# ButtonBreakout.net
KiCad netlist of a schematic drawn in EAGLE
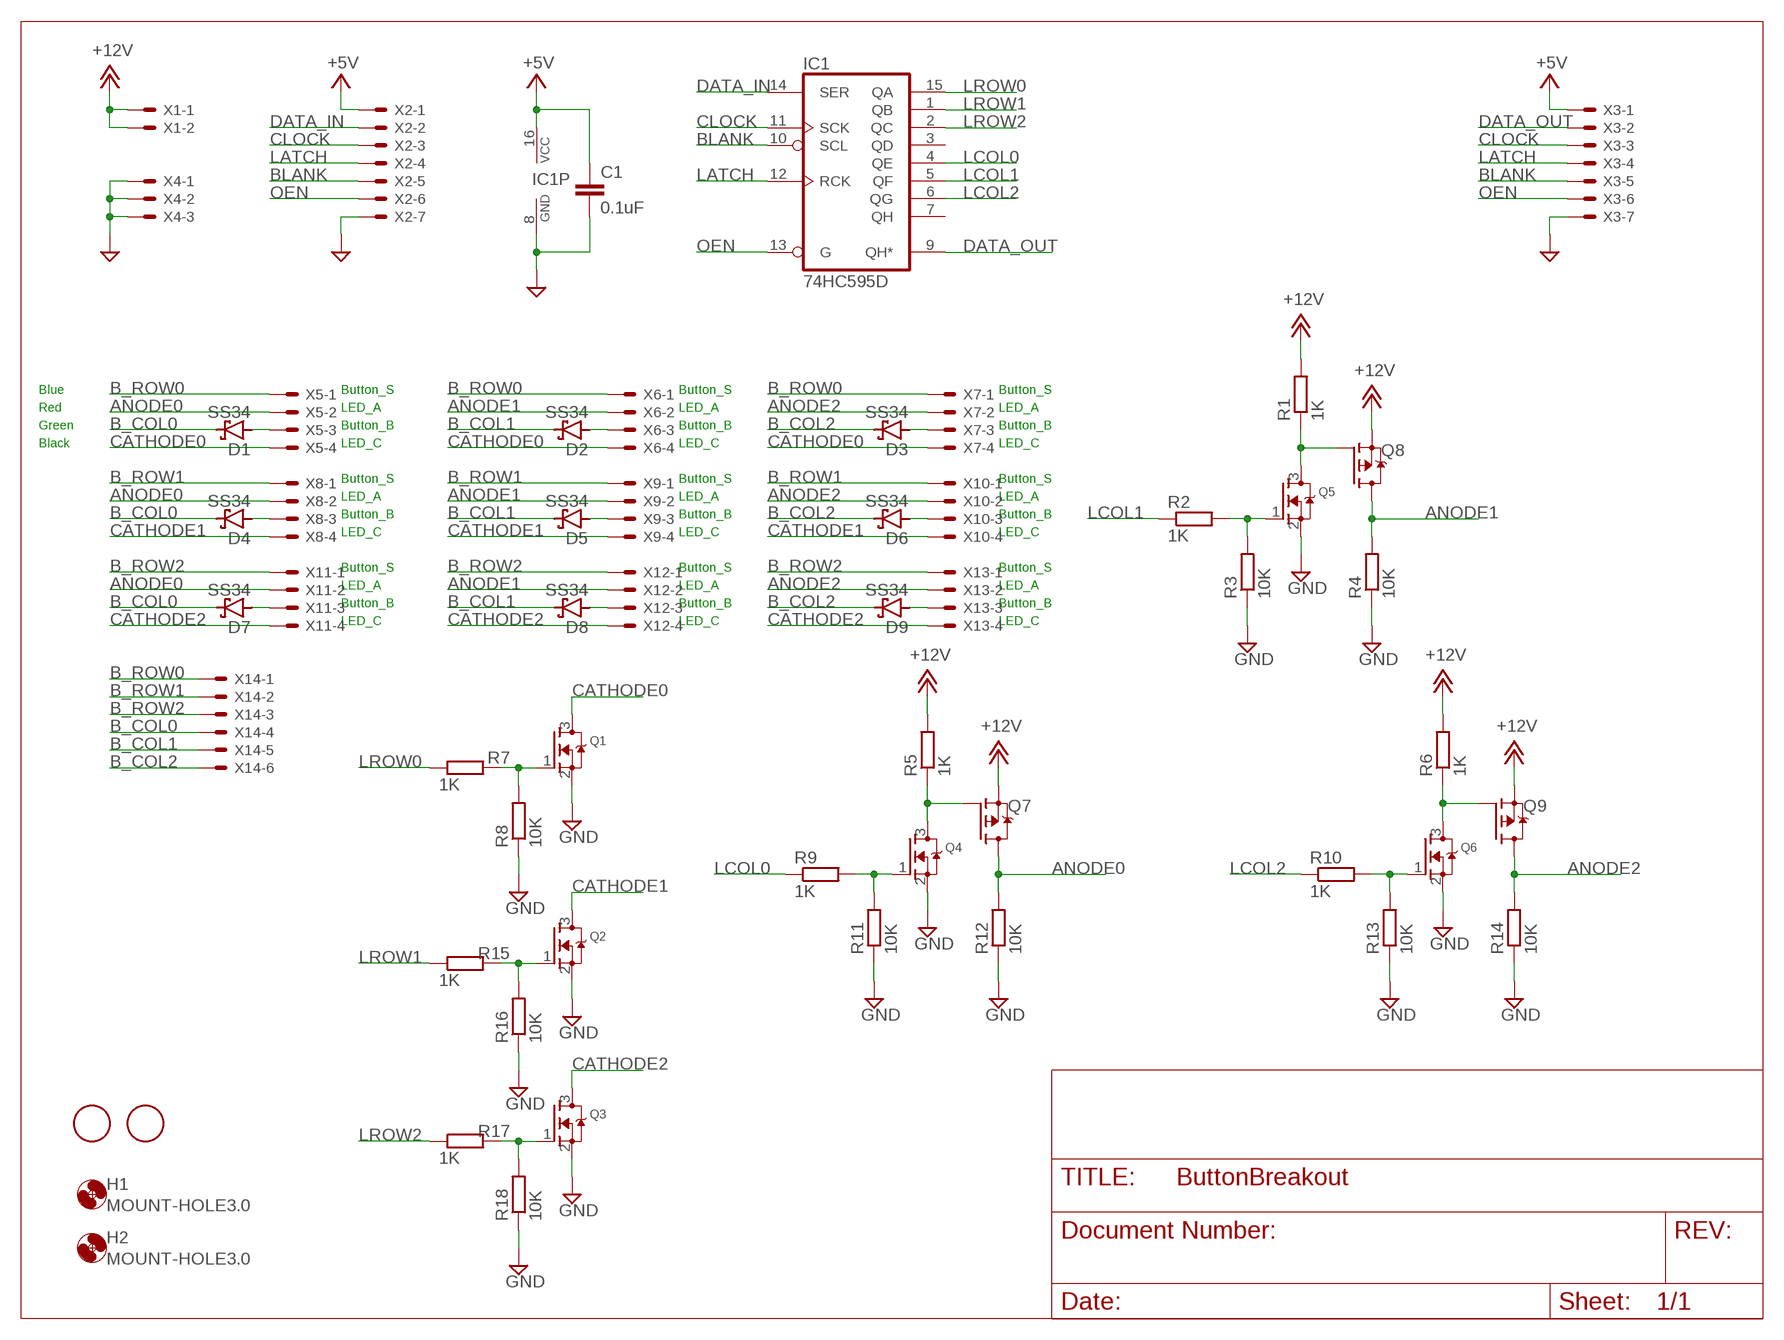
[diagram p0: schematic, sheet 1]

(export (version "E")
  (design (tool "Eeschema 10.0.6"))
  (components
    (comp (ref "C1")
      (value "0.1uF")
      (footprint "eagle-import:C0805")
      (libsource (lib "eagle-import") (part "C-EUC0805"))
    )
    (comp (ref "D1")
      (value "SS34")
      (footprint "eagle-import:SMA")
      (libsource (lib "eagle-import") (part "SS34"))
    )
    (comp (ref "D2")
      (value "SS34")
      (footprint "eagle-import:SMA")
      (libsource (lib "eagle-import") (part "SS34"))
    )
    (comp (ref "D3")
      (value "SS34")
      (footprint "eagle-import:SMA")
      (libsource (lib "eagle-import") (part "SS34"))
    )
    (comp (ref "D4")
      (value "SS34")
      (footprint "eagle-import:SMA")
      (libsource (lib "eagle-import") (part "SS34"))
    )
    (comp (ref "D5")
      (value "SS34")
      (footprint "eagle-import:SMA")
      (libsource (lib "eagle-import") (part "SS34"))
    )
    (comp (ref "D6")
      (value "SS34")
      (footprint "eagle-import:SMA")
      (libsource (lib "eagle-import") (part "SS34"))
    )
    (comp (ref "D7")
      (value "SS34")
      (footprint "eagle-import:SMA")
      (libsource (lib "eagle-import") (part "SS34"))
    )
    (comp (ref "D8")
      (value "SS34")
      (footprint "eagle-import:SMA")
      (libsource (lib "eagle-import") (part "SS34"))
    )
    (comp (ref "D9")
      (value "SS34")
      (footprint "eagle-import:SMA")
      (libsource (lib "eagle-import") (part "SS34"))
    )
    (comp (ref "F1")
      (value "FIDUCIAL")
      (footprint "eagle-import:FIDUCIAL_1MM")
      (libsource (lib "eagle-import") (part "FIDUCIAL"))
    )
    (comp (ref "F2")
      (value "FIDUCIAL")
      (footprint "eagle-import:FIDUCIAL_1MM")
      (libsource (lib "eagle-import") (part "FIDUCIAL"))
    )
    (comp (ref "H1")
      (value "MOUNT-HOLE3.0")
      (footprint "eagle-import:3,0")
      (libsource (lib "eagle-import") (part "MOUNT-HOLE3.0"))
    )
    (comp (ref "H2")
      (value "MOUNT-HOLE3.0")
      (footprint "eagle-import:3,0")
      (libsource (lib "eagle-import") (part "MOUNT-HOLE3.0"))
    )
    (comp (ref "IC1")
      (value "74HC595D")
      (footprint "eagle-import:SO16")
      (libsource (lib "eagle-import") (part "74595DHC"))
    )
    (comp (ref "Q1")
      (value "AO3414SOT23")
      (footprint "eagle-import:SOT95P240X110-3N")
      (libsource (lib "eagle-import") (part "AO3414SOT23"))
    )
    (comp (ref "Q2")
      (value "AO3414SOT23")
      (footprint "eagle-import:SOT95P240X110-3N")
      (libsource (lib "eagle-import") (part "AO3414SOT23"))
    )
    (comp (ref "Q3")
      (value "AO3414SOT23")
      (footprint "eagle-import:SOT95P240X110-3N")
      (libsource (lib "eagle-import") (part "AO3414SOT23"))
    )
    (comp (ref "Q4")
      (value "AO3414SOT23")
      (footprint "eagle-import:SOT95P240X110-3N")
      (libsource (lib "eagle-import") (part "AO3414SOT23"))
    )
    (comp (ref "Q5")
      (value "AO3414SOT23")
      (footprint "eagle-import:SOT95P240X110-3N")
      (libsource (lib "eagle-import") (part "AO3414SOT23"))
    )
    (comp (ref "Q6")
      (value "AO3414SOT23")
      (footprint "eagle-import:SOT95P240X110-3N")
      (libsource (lib "eagle-import") (part "AO3414SOT23"))
    )
    (comp (ref "Q7")
      (value "AO3415")
      (footprint "eagle-import:SOT95P240X110-3N")
      (libsource (lib "eagle-import") (part "AO3415"))
    )
    (comp (ref "Q8")
      (value "AO3415")
      (footprint "eagle-import:SOT95P240X110-3N")
      (libsource (lib "eagle-import") (part "AO3415"))
    )
    (comp (ref "Q9")
      (value "AO3415")
      (footprint "eagle-import:SOT95P240X110-3N")
      (libsource (lib "eagle-import") (part "AO3415"))
    )
    (comp (ref "R1")
      (value "1K")
      (footprint "eagle-import:R0805")
      (libsource (lib "eagle-import") (part "R-EU_R0805"))
    )
    (comp (ref "R2")
      (value "1K")
      (footprint "eagle-import:R0805")
      (libsource (lib "eagle-import") (part "R-EU_R0805"))
    )
    (comp (ref "R3")
      (value "10K")
      (footprint "eagle-import:R0805")
      (libsource (lib "eagle-import") (part "R-EU_R0805"))
    )
    (comp (ref "R4")
      (value "10K")
      (footprint "eagle-import:R0805")
      (libsource (lib "eagle-import") (part "R-EU_R0805"))
    )
    (comp (ref "R5")
      (value "1K")
      (footprint "eagle-import:R0805")
      (libsource (lib "eagle-import") (part "R-EU_R0805"))
    )
    (comp (ref "R6")
      (value "1K")
      (footprint "eagle-import:R0805")
      (libsource (lib "eagle-import") (part "R-EU_R0805"))
    )
    (comp (ref "R7")
      (value "1K")
      (footprint "eagle-import:R0805")
      (libsource (lib "eagle-import") (part "R-EU_R0805"))
    )
    (comp (ref "R8")
      (value "10K")
      (footprint "eagle-import:R0805")
      (libsource (lib "eagle-import") (part "R-EU_R0805"))
    )
    (comp (ref "R9")
      (value "1K")
      (footprint "eagle-import:R0805")
      (libsource (lib "eagle-import") (part "R-EU_R0805"))
    )
    (comp (ref "R10")
      (value "1K")
      (footprint "eagle-import:R0805")
      (libsource (lib "eagle-import") (part "R-EU_R0805"))
    )
    (comp (ref "R11")
      (value "10K")
      (footprint "eagle-import:R0805")
      (libsource (lib "eagle-import") (part "R-EU_R0805"))
    )
    (comp (ref "R12")
      (value "10K")
      (footprint "eagle-import:R0805")
      (libsource (lib "eagle-import") (part "R-EU_R0805"))
    )
    (comp (ref "R13")
      (value "10K")
      (footprint "eagle-import:R0805")
      (libsource (lib "eagle-import") (part "R-EU_R0805"))
    )
    (comp (ref "R14")
      (value "10K")
      (footprint "eagle-import:R0805")
      (libsource (lib "eagle-import") (part "R-EU_R0805"))
    )
    (comp (ref "R15")
      (value "1K")
      (footprint "eagle-import:R0805")
      (libsource (lib "eagle-import") (part "R-EU_R0805"))
    )
    (comp (ref "R16")
      (value "10K")
      (footprint "eagle-import:R0805")
      (libsource (lib "eagle-import") (part "R-EU_R0805"))
    )
    (comp (ref "R17")
      (value "1K")
      (footprint "eagle-import:R0805")
      (libsource (lib "eagle-import") (part "R-EU_R0805"))
    )
    (comp (ref "R18")
      (value "10K")
      (footprint "eagle-import:R0805")
      (libsource (lib "eagle-import") (part "R-EU_R0805"))
    )
    (comp (ref "X1")
      (value "JST-XH-02-PIN-LONG-PAD")
      (footprint "eagle-import:JST-XH-02-PACKAGE-LONG-PAD")
      (libsource (lib "eagle-import") (part "JST-XH-02-PIN-LONG-PAD"))
    )
    (comp (ref "X2")
      (value "JST-XH-07-PIN-LONG-PAD")
      (footprint "eagle-import:JST-XH-07-PACKAGE-LONG-PAD")
      (libsource (lib "eagle-import") (part "JST-XH-07-PIN-LONG-PAD"))
    )
    (comp (ref "X3")
      (value "JST-XH-07-PIN-LONG-PAD")
      (footprint "eagle-import:JST-XH-07-PACKAGE-LONG-PAD")
      (libsource (lib "eagle-import") (part "JST-XH-07-PIN-LONG-PAD"))
    )
    (comp (ref "X4")
      (value "JST-XH-03-PIN-LONG-PAD")
      (footprint "eagle-import:JST-XH-03-PACKAGE-LONG-PAD")
      (libsource (lib "eagle-import") (part "JST-XH-03-PIN-LONG-PAD"))
    )
    (comp (ref "X5")
      (value "JST-XH-04-PIN-LONG-PAD")
      (footprint "eagle-import:JST-XH-04-PACKAGE-LONG-PAD")
      (libsource (lib "eagle-import") (part "JST-XH-04-PIN-LONG-PAD"))
    )
    (comp (ref "X6")
      (value "JST-XH-04-PIN-LONG-PAD")
      (footprint "eagle-import:JST-XH-04-PACKAGE-LONG-PAD")
      (libsource (lib "eagle-import") (part "JST-XH-04-PIN-LONG-PAD"))
    )
    (comp (ref "X7")
      (value "JST-XH-04-PIN-LONG-PAD")
      (footprint "eagle-import:JST-XH-04-PACKAGE-LONG-PAD")
      (libsource (lib "eagle-import") (part "JST-XH-04-PIN-LONG-PAD"))
    )
    (comp (ref "X8")
      (value "JST-XH-04-PIN-LONG-PAD")
      (footprint "eagle-import:JST-XH-04-PACKAGE-LONG-PAD")
      (libsource (lib "eagle-import") (part "JST-XH-04-PIN-LONG-PAD"))
    )
    (comp (ref "X9")
      (value "JST-XH-04-PIN-LONG-PAD")
      (footprint "eagle-import:JST-XH-04-PACKAGE-LONG-PAD")
      (libsource (lib "eagle-import") (part "JST-XH-04-PIN-LONG-PAD"))
    )
    (comp (ref "X10")
      (value "JST-XH-04-PIN-LONG-PAD")
      (footprint "eagle-import:JST-XH-04-PACKAGE-LONG-PAD")
      (libsource (lib "eagle-import") (part "JST-XH-04-PIN-LONG-PAD"))
    )
    (comp (ref "X11")
      (value "JST-XH-04-PIN-LONG-PAD")
      (footprint "eagle-import:JST-XH-04-PACKAGE-LONG-PAD")
      (libsource (lib "eagle-import") (part "JST-XH-04-PIN-LONG-PAD"))
    )
    (comp (ref "X12")
      (value "JST-XH-04-PIN-LONG-PAD")
      (footprint "eagle-import:JST-XH-04-PACKAGE-LONG-PAD")
      (libsource (lib "eagle-import") (part "JST-XH-04-PIN-LONG-PAD"))
    )
    (comp (ref "X13")
      (value "JST-XH-04-PIN-LONG-PAD")
      (footprint "eagle-import:JST-XH-04-PACKAGE-LONG-PAD")
      (libsource (lib "eagle-import") (part "JST-XH-04-PIN-LONG-PAD"))
    )
    (comp (ref "X14")
      (value "JST-XH-06-PIN-LONG-PAD")
      (footprint "eagle-import:JST-XH-06-PACKAGE-LONG-PAD")
      (libsource (lib "eagle-import") (part "JST-XH-06-PIN-LONG-PAD"))
    )
  )
  (nets
    (net (code "1") (name "+5V") (class "Default")
      (node (ref "C1") (pin "1") (pinfunction "1_1") (pintype "passive"))
      (node (ref "IC1") (pin "16") (pinfunction "VCC_16") (pintype "power_in"))
      (node (ref "X2") (pin "1") (pinfunction "S_1") (pintype "passive"))
      (node (ref "X3") (pin "1") (pinfunction "S_1") (pintype "passive"))
    )
    (net (code "2") (name "+12V") (class "Default")
      (node (ref "Q7") (pin "2") (pinfunction "S_2") (pintype "passive"))
      (node (ref "Q8") (pin "2") (pinfunction "S_2") (pintype "passive"))
      (node (ref "Q9") (pin "2") (pinfunction "S_2") (pintype "passive"))
      (node (ref "R1") (pin "2") (pinfunction "2_2") (pintype "passive"))
      (node (ref "R5") (pin "2") (pinfunction "2_2") (pintype "passive"))
      (node (ref "R6") (pin "2") (pinfunction "2_2") (pintype "passive"))
      (node (ref "X1") (pin "1") (pinfunction "S_1") (pintype "passive"))
      (node (ref "X1") (pin "2") (pinfunction "S_2") (pintype "passive"))
    )
    (net (code "3") (name "/ANODE0") (class "Default")
      (node (ref "Q7") (pin "3") (pinfunction "D_3") (pintype "passive"))
      (node (ref "R12") (pin "2") (pinfunction "2_2") (pintype "passive"))
      (node (ref "X11") (pin "2") (pinfunction "S_2") (pintype "passive"))
      (node (ref "X5") (pin "2") (pinfunction "S_2") (pintype "passive"))
      (node (ref "X8") (pin "2") (pinfunction "S_2") (pintype "passive"))
    )
    (net (code "4") (name "/ANODE1") (class "Default")
      (node (ref "Q8") (pin "3") (pinfunction "D_3") (pintype "passive"))
      (node (ref "R4") (pin "2") (pinfunction "2_2") (pintype "passive"))
      (node (ref "X12") (pin "2") (pinfunction "S_2") (pintype "passive"))
      (node (ref "X6") (pin "2") (pinfunction "S_2") (pintype "passive"))
      (node (ref "X9") (pin "2") (pinfunction "S_2") (pintype "passive"))
    )
    (net (code "5") (name "/ANODE2") (class "Default")
      (node (ref "Q9") (pin "3") (pinfunction "D_3") (pintype "passive"))
      (node (ref "R14") (pin "2") (pinfunction "2_2") (pintype "passive"))
      (node (ref "X10") (pin "2") (pinfunction "S_2") (pintype "passive"))
      (node (ref "X13") (pin "2") (pinfunction "S_2") (pintype "passive"))
      (node (ref "X7") (pin "2") (pinfunction "S_2") (pintype "passive"))
    )
    (net (code "6") (name "/BLANK") (class "Default")
      (node (ref "IC1") (pin "10") (pinfunction "SCL_10") (pintype "input"))
      (node (ref "X2") (pin "5") (pinfunction "S_5") (pintype "passive"))
      (node (ref "X3") (pin "5") (pinfunction "S_5") (pintype "passive"))
    )
    (net (code "7") (name "/B_COL0") (class "Default")
      (node (ref "D1") (pin "C") (pinfunction "C_C") (pintype "passive"))
      (node (ref "D4") (pin "C") (pinfunction "C_C") (pintype "passive"))
      (node (ref "D7") (pin "C") (pinfunction "C_C") (pintype "passive"))
      (node (ref "X14") (pin "4") (pinfunction "S_4") (pintype "passive"))
    )
    (net (code "8") (name "/B_COL1") (class "Default")
      (node (ref "D2") (pin "C") (pinfunction "C_C") (pintype "passive"))
      (node (ref "D5") (pin "C") (pinfunction "C_C") (pintype "passive"))
      (node (ref "D8") (pin "C") (pinfunction "C_C") (pintype "passive"))
      (node (ref "X14") (pin "5") (pinfunction "S_5") (pintype "passive"))
    )
    (net (code "9") (name "/B_COL2") (class "Default")
      (node (ref "D3") (pin "C") (pinfunction "C_C") (pintype "passive"))
      (node (ref "D6") (pin "C") (pinfunction "C_C") (pintype "passive"))
      (node (ref "D9") (pin "C") (pinfunction "C_C") (pintype "passive"))
      (node (ref "X14") (pin "6") (pinfunction "S_6") (pintype "passive"))
    )
    (net (code "10") (name "/B_ROW0") (class "Default")
      (node (ref "X14") (pin "1") (pinfunction "S_1") (pintype "passive"))
      (node (ref "X5") (pin "1") (pinfunction "S_1") (pintype "passive"))
      (node (ref "X6") (pin "1") (pinfunction "S_1") (pintype "passive"))
      (node (ref "X7") (pin "1") (pinfunction "S_1") (pintype "passive"))
    )
    (net (code "11") (name "/B_ROW1") (class "Default")
      (node (ref "X10") (pin "1") (pinfunction "S_1") (pintype "passive"))
      (node (ref "X14") (pin "2") (pinfunction "S_2") (pintype "passive"))
      (node (ref "X8") (pin "1") (pinfunction "S_1") (pintype "passive"))
      (node (ref "X9") (pin "1") (pinfunction "S_1") (pintype "passive"))
    )
    (net (code "12") (name "/B_ROW2") (class "Default")
      (node (ref "X11") (pin "1") (pinfunction "S_1") (pintype "passive"))
      (node (ref "X12") (pin "1") (pinfunction "S_1") (pintype "passive"))
      (node (ref "X13") (pin "1") (pinfunction "S_1") (pintype "passive"))
      (node (ref "X14") (pin "3") (pinfunction "S_3") (pintype "passive"))
    )
    (net (code "13") (name "/CATHODE0") (class "Default")
      (node (ref "Q1") (pin "3") (pinfunction "D_3") (pintype "bidirectional"))
      (node (ref "X5") (pin "4") (pinfunction "S_4") (pintype "passive"))
      (node (ref "X6") (pin "4") (pinfunction "S_4") (pintype "passive"))
      (node (ref "X7") (pin "4") (pinfunction "S_4") (pintype "passive"))
    )
    (net (code "14") (name "/CATHODE1") (class "Default")
      (node (ref "Q2") (pin "3") (pinfunction "D_3") (pintype "bidirectional"))
      (node (ref "X10") (pin "4") (pinfunction "S_4") (pintype "passive"))
      (node (ref "X8") (pin "4") (pinfunction "S_4") (pintype "passive"))
      (node (ref "X9") (pin "4") (pinfunction "S_4") (pintype "passive"))
    )
    (net (code "15") (name "/CATHODE2") (class "Default")
      (node (ref "Q3") (pin "3") (pinfunction "D_3") (pintype "bidirectional"))
      (node (ref "X11") (pin "4") (pinfunction "S_4") (pintype "passive"))
      (node (ref "X12") (pin "4") (pinfunction "S_4") (pintype "passive"))
      (node (ref "X13") (pin "4") (pinfunction "S_4") (pintype "passive"))
    )
    (net (code "16") (name "/CLOCK") (class "Default")
      (node (ref "IC1") (pin "11") (pinfunction "SCK_11") (pintype "input"))
      (node (ref "X2") (pin "3") (pinfunction "S_3") (pintype "passive"))
      (node (ref "X3") (pin "3") (pinfunction "S_3") (pintype "passive"))
    )
    (net (code "17") (name "/DATA_IN") (class "Default")
      (node (ref "IC1") (pin "14") (pinfunction "SER_14") (pintype "input"))
      (node (ref "X2") (pin "2") (pinfunction "S_2") (pintype "passive"))
    )
    (net (code "18") (name "/DATA_OUT") (class "Default")
      (node (ref "IC1") (pin "9") (pinfunction "QH*_9") (pintype "tri_state"))
      (node (ref "X3") (pin "2") (pinfunction "S_2") (pintype "passive"))
    )
    (net (code "19") (name "/LATCH") (class "Default")
      (node (ref "IC1") (pin "12") (pinfunction "RCK_12") (pintype "input"))
      (node (ref "X2") (pin "4") (pinfunction "S_4") (pintype "passive"))
      (node (ref "X3") (pin "4") (pinfunction "S_4") (pintype "passive"))
    )
    (net (code "20") (name "/LCOL0") (class "Default")
      (node (ref "IC1") (pin "4") (pinfunction "QE_4") (pintype "tri_state"))
      (node (ref "R9") (pin "1") (pinfunction "1_1") (pintype "passive"))
    )
    (net (code "21") (name "/LCOL1") (class "Default")
      (node (ref "IC1") (pin "5") (pinfunction "QF_5") (pintype "tri_state"))
      (node (ref "R2") (pin "1") (pinfunction "1_1") (pintype "passive"))
    )
    (net (code "22") (name "/LCOL2") (class "Default")
      (node (ref "IC1") (pin "6") (pinfunction "QG_6") (pintype "tri_state"))
      (node (ref "R10") (pin "1") (pinfunction "1_1") (pintype "passive"))
    )
    (net (code "23") (name "/LROW0") (class "Default")
      (node (ref "IC1") (pin "15") (pinfunction "QA_15") (pintype "tri_state"))
      (node (ref "R7") (pin "1") (pinfunction "1_1") (pintype "passive"))
    )
    (net (code "24") (name "/LROW1") (class "Default")
      (node (ref "IC1") (pin "1") (pinfunction "QB_1") (pintype "tri_state"))
      (node (ref "R15") (pin "1") (pinfunction "1_1") (pintype "passive"))
    )
    (net (code "25") (name "/LROW2") (class "Default")
      (node (ref "IC1") (pin "2") (pinfunction "QC_2") (pintype "tri_state"))
      (node (ref "R17") (pin "1") (pinfunction "1_1") (pintype "passive"))
    )
    (net (code "26") (name "/OEN") (class "Default")
      (node (ref "IC1") (pin "13") (pinfunction "G_13") (pintype "input"))
      (node (ref "X2") (pin "6") (pinfunction "S_6") (pintype "passive"))
      (node (ref "X3") (pin "6") (pinfunction "S_6") (pintype "passive"))
    )
    (net (code "27") (name "GND") (class "Default")
      (node (ref "C1") (pin "2") (pinfunction "2_2") (pintype "passive"))
      (node (ref "IC1") (pin "8") (pinfunction "GND_8") (pintype "power_in"))
      (node (ref "Q1") (pin "2") (pinfunction "S_2") (pintype "bidirectional"))
      (node (ref "Q2") (pin "2") (pinfunction "S_2") (pintype "bidirectional"))
      (node (ref "Q3") (pin "2") (pinfunction "S_2") (pintype "bidirectional"))
      (node (ref "Q4") (pin "2") (pinfunction "S_2") (pintype "bidirectional"))
      (node (ref "Q5") (pin "2") (pinfunction "S_2") (pintype "bidirectional"))
      (node (ref "Q6") (pin "2") (pinfunction "S_2") (pintype "bidirectional"))
      (node (ref "R11") (pin "1") (pinfunction "1_1") (pintype "passive"))
      (node (ref "R12") (pin "1") (pinfunction "1_1") (pintype "passive"))
      (node (ref "R13") (pin "1") (pinfunction "1_1") (pintype "passive"))
      (node (ref "R14") (pin "1") (pinfunction "1_1") (pintype "passive"))
      (node (ref "R16") (pin "1") (pinfunction "1_1") (pintype "passive"))
      (node (ref "R18") (pin "1") (pinfunction "1_1") (pintype "passive"))
      (node (ref "R3") (pin "1") (pinfunction "1_1") (pintype "passive"))
      (node (ref "R4") (pin "1") (pinfunction "1_1") (pintype "passive"))
      (node (ref "R8") (pin "1") (pinfunction "1_1") (pintype "passive"))
      (node (ref "X2") (pin "7") (pinfunction "S_7") (pintype "passive"))
      (node (ref "X3") (pin "7") (pinfunction "S_7") (pintype "passive"))
      (node (ref "X4") (pin "1") (pinfunction "S_1") (pintype "passive"))
      (node (ref "X4") (pin "2") (pinfunction "S_2") (pintype "passive"))
      (node (ref "X4") (pin "3") (pinfunction "S_3") (pintype "passive"))
    )
    (net (code "28") (name "Net-(Q1-G)") (class "Default")
      (node (ref "Q1") (pin "1") (pinfunction "G_1") (pintype "bidirectional"))
      (node (ref "R7") (pin "2") (pinfunction "2_2") (pintype "passive"))
      (node (ref "R8") (pin "2") (pinfunction "2_2") (pintype "passive"))
    )
    (net (code "29") (name "Net-(Q2-G)") (class "Default")
      (node (ref "Q2") (pin "1") (pinfunction "G_1") (pintype "bidirectional"))
      (node (ref "R15") (pin "2") (pinfunction "2_2") (pintype "passive"))
      (node (ref "R16") (pin "2") (pinfunction "2_2") (pintype "passive"))
    )
    (net (code "30") (name "Net-(Q3-G)") (class "Default")
      (node (ref "Q3") (pin "1") (pinfunction "G_1") (pintype "bidirectional"))
      (node (ref "R17") (pin "2") (pinfunction "2_2") (pintype "passive"))
      (node (ref "R18") (pin "2") (pinfunction "2_2") (pintype "passive"))
    )
    (net (code "31") (name "Net-(Q4-D)") (class "Default")
      (node (ref "Q4") (pin "3") (pinfunction "D_3") (pintype "bidirectional"))
      (node (ref "Q7") (pin "1") (pinfunction "G_1") (pintype "passive"))
      (node (ref "R5") (pin "1") (pinfunction "1_1") (pintype "passive"))
    )
    (net (code "32") (name "Net-(Q4-G)") (class "Default")
      (node (ref "Q4") (pin "1") (pinfunction "G_1") (pintype "bidirectional"))
      (node (ref "R11") (pin "2") (pinfunction "2_2") (pintype "passive"))
      (node (ref "R9") (pin "2") (pinfunction "2_2") (pintype "passive"))
    )
    (net (code "33") (name "Net-(Q5-D)") (class "Default")
      (node (ref "Q5") (pin "3") (pinfunction "D_3") (pintype "bidirectional"))
      (node (ref "Q8") (pin "1") (pinfunction "G_1") (pintype "passive"))
      (node (ref "R1") (pin "1") (pinfunction "1_1") (pintype "passive"))
    )
    (net (code "34") (name "Net-(Q5-G)") (class "Default")
      (node (ref "Q5") (pin "1") (pinfunction "G_1") (pintype "bidirectional"))
      (node (ref "R2") (pin "2") (pinfunction "2_2") (pintype "passive"))
      (node (ref "R3") (pin "2") (pinfunction "2_2") (pintype "passive"))
    )
    (net (code "35") (name "Net-(Q6-D)") (class "Default")
      (node (ref "Q6") (pin "3") (pinfunction "D_3") (pintype "bidirectional"))
      (node (ref "Q9") (pin "1") (pinfunction "G_1") (pintype "passive"))
      (node (ref "R6") (pin "1") (pinfunction "1_1") (pintype "passive"))
    )
    (net (code "36") (name "Net-(Q6-G)") (class "Default")
      (node (ref "Q6") (pin "1") (pinfunction "G_1") (pintype "bidirectional"))
      (node (ref "R10") (pin "2") (pinfunction "2_2") (pintype "passive"))
      (node (ref "R13") (pin "2") (pinfunction "2_2") (pintype "passive"))
    )
    (net (code "37") (name "Net-(X5C-S)") (class "Default")
      (node (ref "D1") (pin "A") (pinfunction "A_A") (pintype "passive"))
      (node (ref "X5") (pin "3") (pinfunction "S_3") (pintype "passive"))
    )
    (net (code "38") (name "Net-(X6C-S)") (class "Default")
      (node (ref "D2") (pin "A") (pinfunction "A_A") (pintype "passive"))
      (node (ref "X6") (pin "3") (pinfunction "S_3") (pintype "passive"))
    )
    (net (code "39") (name "Net-(X7C-S)") (class "Default")
      (node (ref "D3") (pin "A") (pinfunction "A_A") (pintype "passive"))
      (node (ref "X7") (pin "3") (pinfunction "S_3") (pintype "passive"))
    )
    (net (code "40") (name "Net-(X8C-S)") (class "Default")
      (node (ref "D4") (pin "A") (pinfunction "A_A") (pintype "passive"))
      (node (ref "X8") (pin "3") (pinfunction "S_3") (pintype "passive"))
    )
    (net (code "41") (name "Net-(X9C-S)") (class "Default")
      (node (ref "D5") (pin "A") (pinfunction "A_A") (pintype "passive"))
      (node (ref "X9") (pin "3") (pinfunction "S_3") (pintype "passive"))
    )
    (net (code "42") (name "Net-(X10C-S)") (class "Default")
      (node (ref "D6") (pin "A") (pinfunction "A_A") (pintype "passive"))
      (node (ref "X10") (pin "3") (pinfunction "S_3") (pintype "passive"))
    )
    (net (code "43") (name "Net-(X11C-S)") (class "Default")
      (node (ref "D7") (pin "A") (pinfunction "A_A") (pintype "passive"))
      (node (ref "X11") (pin "3") (pinfunction "S_3") (pintype "passive"))
    )
    (net (code "44") (name "Net-(X12C-S)") (class "Default")
      (node (ref "D8") (pin "A") (pinfunction "A_A") (pintype "passive"))
      (node (ref "X12") (pin "3") (pinfunction "S_3") (pintype "passive"))
    )
    (net (code "45") (name "Net-(X13C-S)") (class "Default")
      (node (ref "D9") (pin "A") (pinfunction "A_A") (pintype "passive"))
      (node (ref "X13") (pin "3") (pinfunction "S_3") (pintype "passive"))
    )
    (net (code "46") (name "unconnected-(IC1A-QD-Pad3)") (class "Default")
      (node (ref "IC1") (pin "3") (pinfunction "QD_3") (pintype "tri_state"))
    )
    (net (code "47") (name "unconnected-(IC1A-QH-Pad7)") (class "Default")
      (node (ref "IC1") (pin "7") (pinfunction "QH_7") (pintype "tri_state"))
    )
  )
)
